# GDEnvSensorNode_Programmer.net
KiCad netlist of a schematic drawn in EAGLE
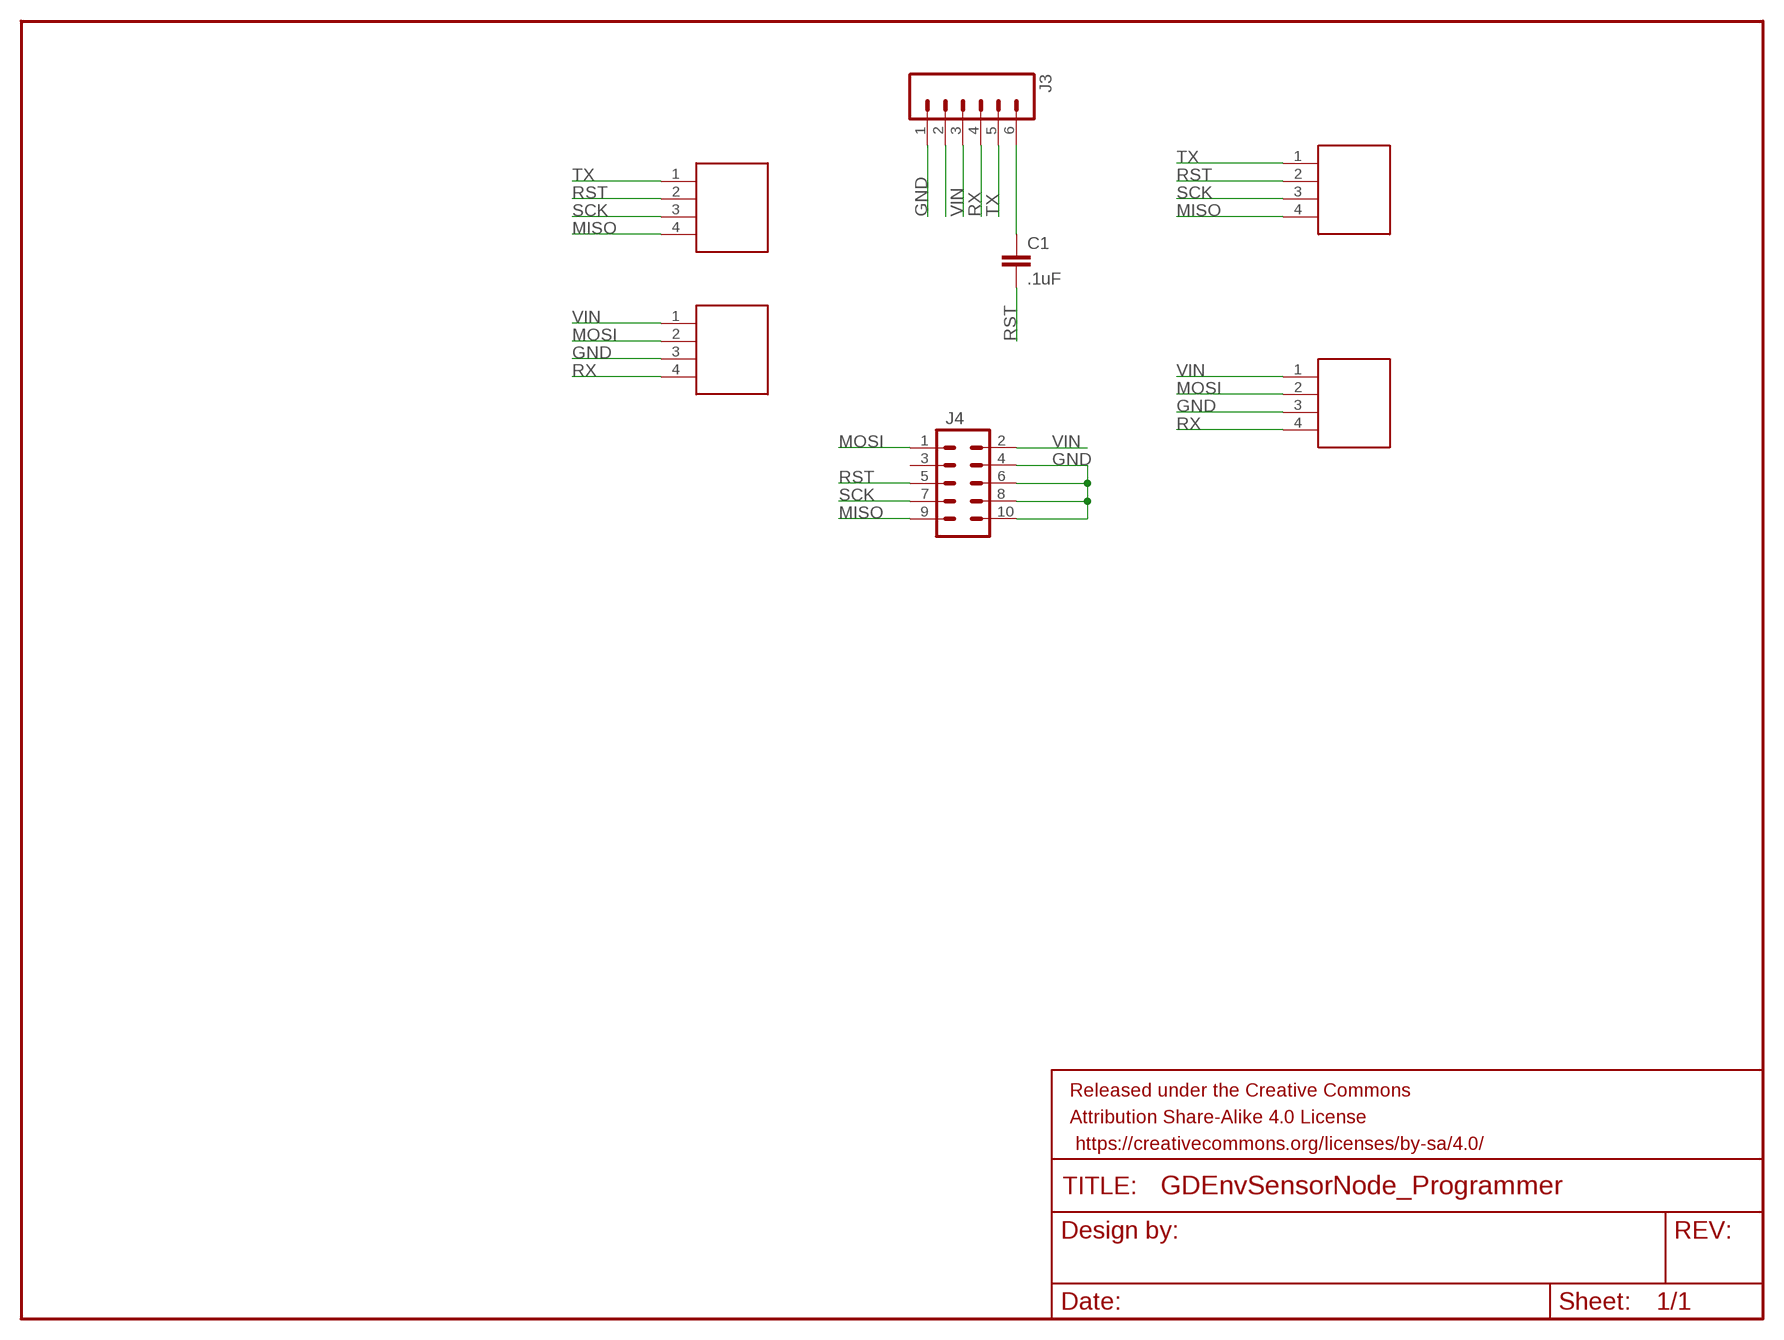
[diagram p0: schematic, sheet 1]

(export (version "E")
  (design (tool "Eeschema 10.0.6"))
  (components
    (comp (ref "C1")
      (value ".1uF")
      (footprint "eagle-import:0805")
      (libsource (lib "eagle-import") (part "CAP0805"))
    )
    (comp (ref "FRAME1")
      (value "FRAME-LETTER")
      (footprint "eagle-import:CREATIVE_COMMONS")
      (libsource (lib "eagle-import") (part "FRAME-LETTER"))
    )
    (comp (ref "J1")
      (value "4X.1IN_POGO_PIN")
      (footprint "eagle-import:4X.1IN_POGO_PIN")
      (libsource (lib "eagle-import") (part "4X.1IN_POGO_PIN"))
    )
    (comp (ref "J2")
      (value "4X.1IN_POGO_PIN")
      (footprint "eagle-import:4X.1IN_POGO_PIN")
      (libsource (lib "eagle-import") (part "4X.1IN_POGO_PIN"))
    )
    (comp (ref "J3")
      (value "M06LONGPADS")
      (footprint "eagle-import:1X06_LONGPADS")
      (libsource (lib "eagle-import") (part "M06LONGPADS"))
    )
    (comp (ref "J4")
      (value "M05X2PTH")
      (footprint "eagle-import:AVR_ICSP")
      (libsource (lib "eagle-import") (part "M05X2PTH"))
    )
    (comp (ref "J5")
      (value "4X.1IN_POGO_PIN")
      (footprint "eagle-import:4X.1IN_POGO_PIN")
      (libsource (lib "eagle-import") (part "4X.1IN_POGO_PIN"))
    )
    (comp (ref "J6")
      (value "4X.1IN_POGO_PIN")
      (footprint "eagle-import:4X.1IN_POGO_PIN")
      (libsource (lib "eagle-import") (part "4X.1IN_POGO_PIN"))
    )
  )
  (nets
    (net (code "1") (name "/GND") (class "Default")
      (node (ref "J2") (pin "3") (pinfunction "3_3") (pintype "bidirectional"))
      (node (ref "J3") (pin "1") (pinfunction "1_1") (pintype "passive"))
      (node (ref "J4") (pin "10") (pinfunction "10_10") (pintype "passive"))
      (node (ref "J4") (pin "4") (pinfunction "4_4") (pintype "passive"))
      (node (ref "J4") (pin "6") (pinfunction "6_6") (pintype "passive"))
      (node (ref "J4") (pin "8") (pinfunction "8_8") (pintype "passive"))
      (node (ref "J6") (pin "3") (pinfunction "3_3") (pintype "bidirectional"))
    )
    (net (code "2") (name "/MISO") (class "Default")
      (node (ref "J1") (pin "4") (pinfunction "4_4") (pintype "bidirectional"))
      (node (ref "J4") (pin "9") (pinfunction "9_9") (pintype "passive"))
      (node (ref "J5") (pin "4") (pinfunction "4_4") (pintype "bidirectional"))
    )
    (net (code "3") (name "/MOSI") (class "Default")
      (node (ref "J2") (pin "2") (pinfunction "2_2") (pintype "bidirectional"))
      (node (ref "J4") (pin "1") (pinfunction "1_1") (pintype "passive"))
      (node (ref "J6") (pin "2") (pinfunction "2_2") (pintype "bidirectional"))
    )
    (net (code "4") (name "/RST") (class "Default")
      (node (ref "C1") (pin "2") (pinfunction "2_2") (pintype "passive"))
      (node (ref "J1") (pin "2") (pinfunction "2_2") (pintype "bidirectional"))
      (node (ref "J4") (pin "5") (pinfunction "5_5") (pintype "passive"))
      (node (ref "J5") (pin "2") (pinfunction "2_2") (pintype "bidirectional"))
    )
    (net (code "5") (name "/RX") (class "Default")
      (node (ref "J2") (pin "4") (pinfunction "4_4") (pintype "bidirectional"))
      (node (ref "J3") (pin "4") (pinfunction "4_4") (pintype "passive"))
      (node (ref "J6") (pin "4") (pinfunction "4_4") (pintype "bidirectional"))
    )
    (net (code "6") (name "/SCK") (class "Default")
      (node (ref "J1") (pin "3") (pinfunction "3_3") (pintype "bidirectional"))
      (node (ref "J4") (pin "7") (pinfunction "7_7") (pintype "passive"))
      (node (ref "J5") (pin "3") (pinfunction "3_3") (pintype "bidirectional"))
    )
    (net (code "7") (name "/TX") (class "Default")
      (node (ref "J1") (pin "1") (pinfunction "1_1") (pintype "bidirectional"))
      (node (ref "J3") (pin "5") (pinfunction "5_5") (pintype "passive"))
      (node (ref "J5") (pin "1") (pinfunction "1_1") (pintype "bidirectional"))
    )
    (net (code "8") (name "/VIN") (class "Default")
      (node (ref "J2") (pin "1") (pinfunction "1_1") (pintype "bidirectional"))
      (node (ref "J3") (pin "3") (pinfunction "3_3") (pintype "passive"))
      (node (ref "J4") (pin "2") (pinfunction "2_2") (pintype "passive"))
      (node (ref "J6") (pin "1") (pinfunction "1_1") (pintype "bidirectional"))
    )
    (net (code "9") (name "Net-(C1-Pad1)") (class "Default")
      (node (ref "C1") (pin "1") (pinfunction "1_1") (pintype "passive"))
      (node (ref "J3") (pin "6") (pinfunction "6_6") (pintype "passive"))
    )
    (net (code "10") (name "unconnected-(J3-Pad2)") (class "Default")
      (node (ref "J3") (pin "2") (pinfunction "2_2") (pintype "passive"))
    )
    (net (code "11") (name "unconnected-(J4-Pad3)") (class "Default")
      (node (ref "J4") (pin "3") (pinfunction "3_3") (pintype "passive"))
    )
  )
)
